# phy0.net
KiCad netlist of a schematic drawn in Altium Designer
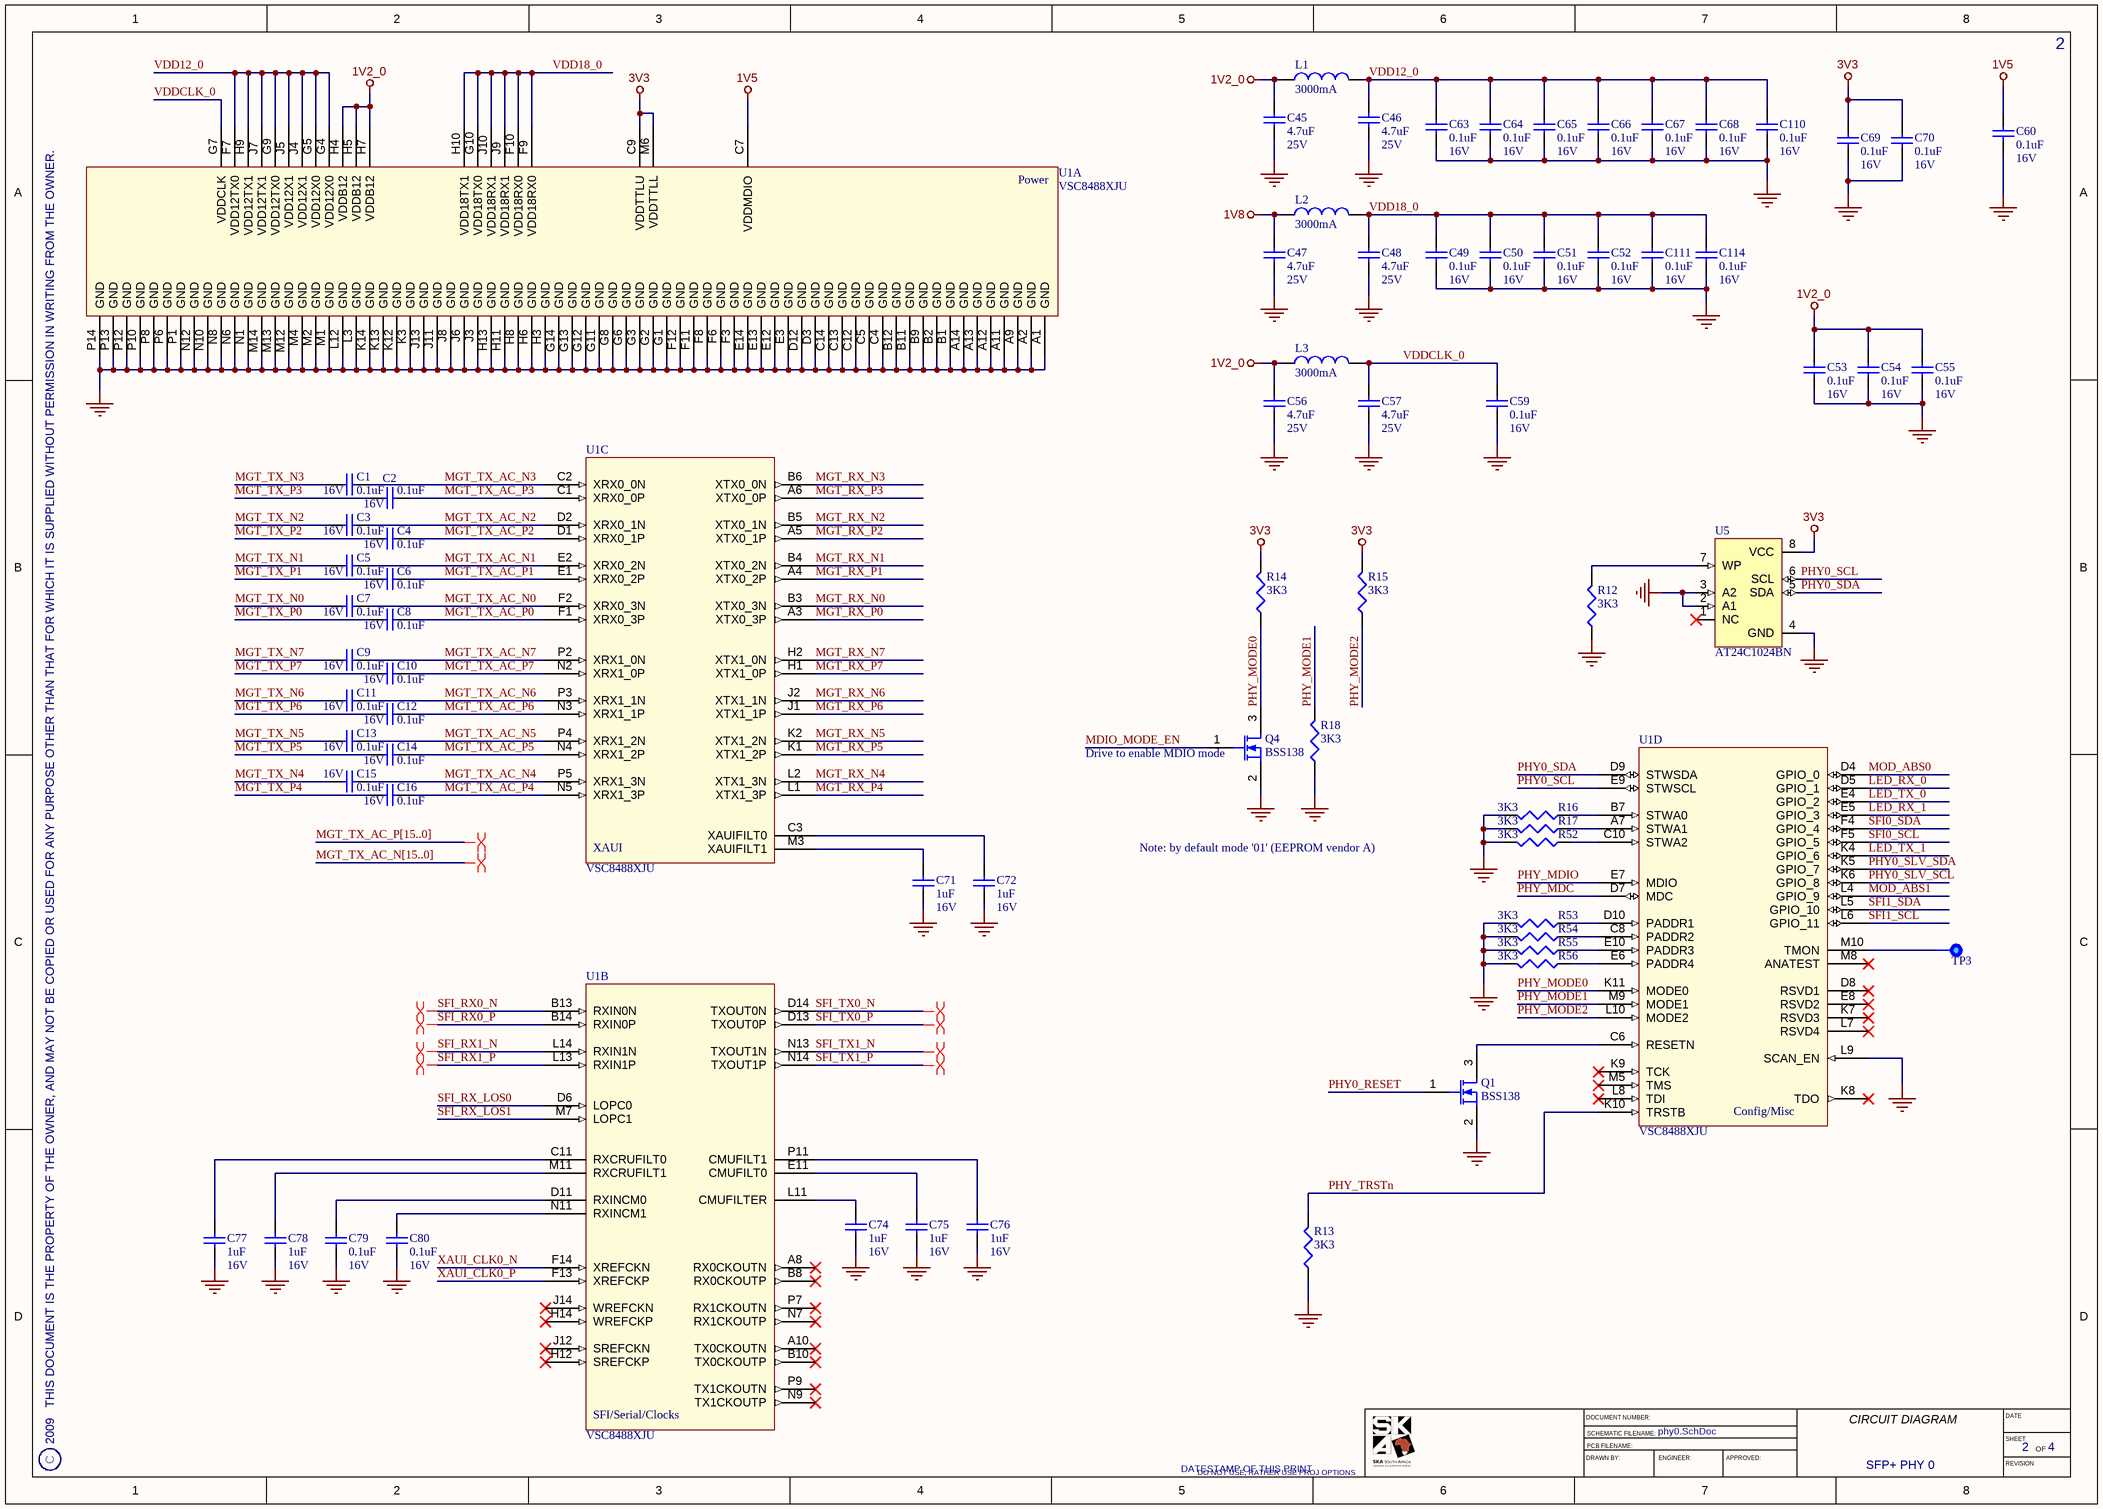
[diagram p0: phy0.SchDoc]

(export (version "E")
  (design (tool "Eeschema 10.0.6"))
  (components
    (comp (ref "C1")
      (value "0.1uF")
      (footprint "CAPC1005X60L")
      (description "0.1uF, Ceramic Capacitor")
      (fields
        (field (name "RATING") "16V")
        (field (name "MANUFACTURER") "VENKEL")
        (field (name "PARTNUM") "C0402X7R160-104KN")
      )
      (libsource (lib "altium_db") (part "CapStd"))
    )
    (comp (ref "C2")
      (value "0.1uF")
      (footprint "CAPC1005X60L")
      (description "0.1uF, Ceramic Capacitor")
      (fields
        (field (name "RATING") "16V")
        (field (name "MANUFACTURER") "VENKEL")
        (field (name "PARTNUM") "C0402X7R160-104KN")
      )
      (libsource (lib "altium_db") (part "CapStd"))
    )
    (comp (ref "C3")
      (value "0.1uF")
      (footprint "CAPC1005X60L")
      (description "0.1uF, Ceramic Capacitor")
      (fields
        (field (name "RATING") "16V")
        (field (name "MANUFACTURER") "VENKEL")
        (field (name "PARTNUM") "C0402X7R160-104KN")
      )
      (libsource (lib "altium_db") (part "CapStd"))
    )
    (comp (ref "C4")
      (value "0.1uF")
      (footprint "CAPC1005X60L")
      (description "0.1uF, Ceramic Capacitor")
      (fields
        (field (name "RATING") "16V")
        (field (name "MANUFACTURER") "VENKEL")
        (field (name "PARTNUM") "C0402X7R160-104KN")
      )
      (libsource (lib "altium_db") (part "CapStd"))
    )
    (comp (ref "C5")
      (value "0.1uF")
      (footprint "CAPC1005X60L")
      (description "0.1uF, Ceramic Capacitor")
      (fields
        (field (name "RATING") "16V")
        (field (name "MANUFACTURER") "VENKEL")
        (field (name "PARTNUM") "C0402X7R160-104KN")
      )
      (libsource (lib "altium_db") (part "CapStd"))
    )
    (comp (ref "C6")
      (value "0.1uF")
      (footprint "CAPC1005X60L")
      (description "0.1uF, Ceramic Capacitor")
      (fields
        (field (name "RATING") "16V")
        (field (name "MANUFACTURER") "VENKEL")
        (field (name "PARTNUM") "C0402X7R160-104KN")
      )
      (libsource (lib "altium_db") (part "CapStd"))
    )
    (comp (ref "C7")
      (value "0.1uF")
      (footprint "CAPC1005X60L")
      (description "0.1uF, Ceramic Capacitor")
      (fields
        (field (name "RATING") "16V")
        (field (name "MANUFACTURER") "VENKEL")
        (field (name "PARTNUM") "C0402X7R160-104KN")
      )
      (libsource (lib "altium_db") (part "CapStd"))
    )
    (comp (ref "C8")
      (value "0.1uF")
      (footprint "CAPC1005X60L")
      (description "0.1uF, Ceramic Capacitor")
      (fields
        (field (name "RATING") "16V")
        (field (name "MANUFACTURER") "VENKEL")
        (field (name "PARTNUM") "C0402X7R160-104KN")
      )
      (libsource (lib "altium_db") (part "CapStd"))
    )
    (comp (ref "C9")
      (value "0.1uF")
      (footprint "CAPC1005X60L")
      (description "0.1uF, Ceramic Capacitor")
      (fields
        (field (name "RATING") "16V")
        (field (name "MANUFACTURER") "VENKEL")
        (field (name "PARTNUM") "C0402X7R160-104KN")
      )
      (libsource (lib "altium_db") (part "CapStd"))
    )
    (comp (ref "C10")
      (value "0.1uF")
      (footprint "CAPC1005X60L")
      (description "0.1uF, Ceramic Capacitor")
      (fields
        (field (name "RATING") "16V")
        (field (name "MANUFACTURER") "VENKEL")
        (field (name "PARTNUM") "C0402X7R160-104KN")
      )
      (libsource (lib "altium_db") (part "CapStd"))
    )
    (comp (ref "C11")
      (value "0.1uF")
      (footprint "CAPC1005X60L")
      (description "0.1uF, Ceramic Capacitor")
      (fields
        (field (name "RATING") "16V")
        (field (name "MANUFACTURER") "VENKEL")
        (field (name "PARTNUM") "C0402X7R160-104KN")
      )
      (libsource (lib "altium_db") (part "CapStd"))
    )
    (comp (ref "C12")
      (value "0.1uF")
      (footprint "CAPC1005X60L")
      (description "0.1uF, Ceramic Capacitor")
      (fields
        (field (name "RATING") "16V")
        (field (name "MANUFACTURER") "VENKEL")
        (field (name "PARTNUM") "C0402X7R160-104KN")
      )
      (libsource (lib "altium_db") (part "CapStd"))
    )
    (comp (ref "C13")
      (value "0.1uF")
      (footprint "CAPC1005X60L")
      (description "0.1uF, Ceramic Capacitor")
      (fields
        (field (name "RATING") "16V")
        (field (name "MANUFACTURER") "VENKEL")
        (field (name "PARTNUM") "C0402X7R160-104KN")
      )
      (libsource (lib "altium_db") (part "CapStd"))
    )
    (comp (ref "C14")
      (value "0.1uF")
      (footprint "CAPC1005X60L")
      (description "0.1uF, Ceramic Capacitor")
      (fields
        (field (name "RATING") "16V")
        (field (name "MANUFACTURER") "VENKEL")
        (field (name "PARTNUM") "C0402X7R160-104KN")
      )
      (libsource (lib "altium_db") (part "CapStd"))
    )
    (comp (ref "C15")
      (value "0.1uF")
      (footprint "CAPC1005X60L")
      (description "0.1uF, Ceramic Capacitor")
      (fields
        (field (name "RATING") "16V")
        (field (name "MANUFACTURER") "VENKEL")
        (field (name "PARTNUM") "C0402X7R160-104KN")
      )
      (libsource (lib "altium_db") (part "CapStd"))
    )
    (comp (ref "C16")
      (value "0.1uF")
      (footprint "CAPC1005X60L")
      (description "0.1uF, Ceramic Capacitor")
      (fields
        (field (name "RATING") "16V")
        (field (name "MANUFACTURER") "VENKEL")
        (field (name "PARTNUM") "C0402X7R160-104KN")
      )
      (libsource (lib "altium_db") (part "CapStd"))
    )
    (comp (ref "C45")
      (value "4.7uF")
      (footprint "CAPC2012X127L")
      (description "4.7uF, Ceramic Capacitor")
      (fields
        (field (name "RATING") "25V")
        (field (name "MANUFACTURER") "MURATA")
        (field (name "PARTNUM") "GRM21BR61E475KA12K")
      )
      (libsource (lib "altium_db") (part "CapStd"))
    )
    (comp (ref "C46")
      (value "4.7uF")
      (footprint "CAPC2012X127L")
      (description "4.7uF, Ceramic Capacitor")
      (fields
        (field (name "RATING") "25V")
        (field (name "MANUFACTURER") "MURATA")
        (field (name "PARTNUM") "GRM21BR61E475KA12K")
      )
      (libsource (lib "altium_db") (part "CapStd"))
    )
    (comp (ref "C47")
      (value "4.7uF")
      (footprint "CAPC2012X127L")
      (description "4.7uF, Ceramic Capacitor")
      (fields
        (field (name "RATING") "25V")
        (field (name "MANUFACTURER") "MURATA")
        (field (name "PARTNUM") "GRM21BR61E475KA12K")
      )
      (libsource (lib "altium_db") (part "CapStd"))
    )
    (comp (ref "C48")
      (value "4.7uF")
      (footprint "CAPC2012X127L")
      (description "4.7uF, Ceramic Capacitor")
      (fields
        (field (name "RATING") "25V")
        (field (name "MANUFACTURER") "MURATA")
        (field (name "PARTNUM") "GRM21BR61E475KA12K")
      )
      (libsource (lib "altium_db") (part "CapStd"))
    )
    (comp (ref "C49")
      (value "0.1uF")
      (footprint "CAPC1005X60L")
      (description "0.1uF, Ceramic Capacitor")
      (fields
        (field (name "RATING") "16V")
        (field (name "MANUFACTURER") "VENKEL")
        (field (name "PARTNUM") "C0402X7R160-104KN")
      )
      (libsource (lib "altium_db") (part "CapStd"))
    )
    (comp (ref "C50")
      (value "0.1uF")
      (footprint "CAPC1005X60L")
      (description "0.1uF, Ceramic Capacitor")
      (fields
        (field (name "RATING") "16V")
        (field (name "MANUFACTURER") "VENKEL")
        (field (name "PARTNUM") "C0402X7R160-104KN")
      )
      (libsource (lib "altium_db") (part "CapStd"))
    )
    (comp (ref "C51")
      (value "0.1uF")
      (footprint "CAPC1005X60L")
      (description "0.1uF, Ceramic Capacitor")
      (fields
        (field (name "RATING") "16V")
        (field (name "MANUFACTURER") "VENKEL")
        (field (name "PARTNUM") "C0402X7R160-104KN")
      )
      (libsource (lib "altium_db") (part "CapStd"))
    )
    (comp (ref "C52")
      (value "0.1uF")
      (footprint "CAPC1005X60L")
      (description "0.1uF, Ceramic Capacitor")
      (fields
        (field (name "RATING") "16V")
        (field (name "MANUFACTURER") "VENKEL")
        (field (name "PARTNUM") "C0402X7R160-104KN")
      )
      (libsource (lib "altium_db") (part "CapStd"))
    )
    (comp (ref "C53")
      (value "0.1uF")
      (footprint "CAPC1005X60L")
      (description "0.1uF, Ceramic Capacitor")
      (fields
        (field (name "RATING") "16V")
        (field (name "MANUFACTURER") "VENKEL")
        (field (name "PARTNUM") "C0402X7R160-104KN")
      )
      (libsource (lib "altium_db") (part "CapStd"))
    )
    (comp (ref "C54")
      (value "0.1uF")
      (footprint "CAPC1005X60L")
      (description "0.1uF, Ceramic Capacitor")
      (fields
        (field (name "RATING") "16V")
        (field (name "MANUFACTURER") "VENKEL")
        (field (name "PARTNUM") "C0402X7R160-104KN")
      )
      (libsource (lib "altium_db") (part "CapStd"))
    )
    (comp (ref "C55")
      (value "0.1uF")
      (footprint "CAPC1005X60L")
      (description "0.1uF, Ceramic Capacitor")
      (fields
        (field (name "RATING") "16V")
        (field (name "MANUFACTURER") "VENKEL")
        (field (name "PARTNUM") "C0402X7R160-104KN")
      )
      (libsource (lib "altium_db") (part "CapStd"))
    )
    (comp (ref "C56")
      (value "4.7uF")
      (footprint "CAPC2012X127L")
      (description "4.7uF, Ceramic Capacitor")
      (fields
        (field (name "RATING") "25V")
        (field (name "MANUFACTURER") "MURATA")
        (field (name "PARTNUM") "GRM21BR61E475KA12K")
      )
      (libsource (lib "altium_db") (part "CapStd"))
    )
    (comp (ref "C57")
      (value "4.7uF")
      (footprint "CAPC2012X127L")
      (description "4.7uF, Ceramic Capacitor")
      (fields
        (field (name "RATING") "25V")
        (field (name "MANUFACTURER") "MURATA")
        (field (name "PARTNUM") "GRM21BR61E475KA12K")
      )
      (libsource (lib "altium_db") (part "CapStd"))
    )
    (comp (ref "C59")
      (value "0.1uF")
      (footprint "CAPC1005X60L")
      (description "0.1uF, Ceramic Capacitor")
      (fields
        (field (name "RATING") "16V")
        (field (name "MANUFACTURER") "VENKEL")
        (field (name "PARTNUM") "C0402X7R160-104KN")
      )
      (libsource (lib "altium_db") (part "CapStd"))
    )
    (comp (ref "C60")
      (value "0.1uF")
      (footprint "CAPC1005X60L")
      (description "0.1uF, Ceramic Capacitor")
      (fields
        (field (name "RATING") "16V")
        (field (name "MANUFACTURER") "VENKEL")
        (field (name "PARTNUM") "C0402X7R160-104KN")
      )
      (libsource (lib "altium_db") (part "CapStd"))
    )
    (comp (ref "C63")
      (value "0.1uF")
      (footprint "CAPC1005X60L")
      (description "0.1uF, Ceramic Capacitor")
      (fields
        (field (name "RATING") "16V")
        (field (name "MANUFACTURER") "VENKEL")
        (field (name "PARTNUM") "C0402X7R160-104KN")
      )
      (libsource (lib "altium_db") (part "CapStd"))
    )
    (comp (ref "C64")
      (value "0.1uF")
      (footprint "CAPC1005X60L")
      (description "0.1uF, Ceramic Capacitor")
      (fields
        (field (name "RATING") "16V")
        (field (name "MANUFACTURER") "VENKEL")
        (field (name "PARTNUM") "C0402X7R160-104KN")
      )
      (libsource (lib "altium_db") (part "CapStd"))
    )
    (comp (ref "C65")
      (value "0.1uF")
      (footprint "CAPC1005X60L")
      (description "0.1uF, Ceramic Capacitor")
      (fields
        (field (name "RATING") "16V")
        (field (name "MANUFACTURER") "VENKEL")
        (field (name "PARTNUM") "C0402X7R160-104KN")
      )
      (libsource (lib "altium_db") (part "CapStd"))
    )
    (comp (ref "C66")
      (value "0.1uF")
      (footprint "CAPC1005X60L")
      (description "0.1uF, Ceramic Capacitor")
      (fields
        (field (name "RATING") "16V")
        (field (name "MANUFACTURER") "VENKEL")
        (field (name "PARTNUM") "C0402X7R160-104KN")
      )
      (libsource (lib "altium_db") (part "CapStd"))
    )
    (comp (ref "C67")
      (value "0.1uF")
      (footprint "CAPC1005X60L")
      (description "0.1uF, Ceramic Capacitor")
      (fields
        (field (name "RATING") "16V")
        (field (name "MANUFACTURER") "VENKEL")
        (field (name "PARTNUM") "C0402X7R160-104KN")
      )
      (libsource (lib "altium_db") (part "CapStd"))
    )
    (comp (ref "C68")
      (value "0.1uF")
      (footprint "CAPC1005X60L")
      (description "0.1uF, Ceramic Capacitor")
      (fields
        (field (name "RATING") "16V")
        (field (name "MANUFACTURER") "VENKEL")
        (field (name "PARTNUM") "C0402X7R160-104KN")
      )
      (libsource (lib "altium_db") (part "CapStd"))
    )
    (comp (ref "C69")
      (value "0.1uF")
      (footprint "CAPC1005X60L")
      (description "0.1uF, Ceramic Capacitor")
      (fields
        (field (name "RATING") "16V")
        (field (name "MANUFACTURER") "VENKEL")
        (field (name "PARTNUM") "C0402X7R160-104KN")
      )
      (libsource (lib "altium_db") (part "CapStd"))
    )
    (comp (ref "C70")
      (value "0.1uF")
      (footprint "CAPC1005X60L")
      (description "0.1uF, Ceramic Capacitor")
      (fields
        (field (name "RATING") "16V")
        (field (name "MANUFACTURER") "VENKEL")
        (field (name "PARTNUM") "C0402X7R160-104KN")
      )
      (libsource (lib "altium_db") (part "CapStd"))
    )
    (comp (ref "C71")
      (value "1uF")
      (footprint "CAPC2012X127L")
      (description "1uF, Ceramic Capacitor")
      (fields
        (field (name "RATING") "16V")
        (field (name "MANUFACTURER") "MURATA")
        (field (name "PARTNUM") "GRM21BR61C105KA01L")
      )
      (libsource (lib "altium_db") (part "CapStd"))
    )
    (comp (ref "C72")
      (value "1uF")
      (footprint "CAPC2012X127L")
      (description "1uF, Ceramic Capacitor")
      (fields
        (field (name "RATING") "16V")
        (field (name "MANUFACTURER") "MURATA")
        (field (name "PARTNUM") "GRM21BR61C105KA01L")
      )
      (libsource (lib "altium_db") (part "CapStd"))
    )
    (comp (ref "C74")
      (value "1uF")
      (footprint "CAPC2012X127L")
      (description "1uF, Ceramic Capacitor")
      (fields
        (field (name "RATING") "16V")
        (field (name "MANUFACTURER") "MURATA")
        (field (name "PARTNUM") "GRM21BR61C105KA01L")
      )
      (libsource (lib "altium_db") (part "CapStd"))
    )
    (comp (ref "C75")
      (value "1uF")
      (footprint "CAPC2012X127L")
      (description "1uF, Ceramic Capacitor")
      (fields
        (field (name "RATING") "16V")
        (field (name "MANUFACTURER") "MURATA")
        (field (name "PARTNUM") "GRM21BR61C105KA01L")
      )
      (libsource (lib "altium_db") (part "CapStd"))
    )
    (comp (ref "C76")
      (value "1uF")
      (footprint "CAPC2012X127L")
      (description "1uF, Ceramic Capacitor")
      (fields
        (field (name "RATING") "16V")
        (field (name "MANUFACTURER") "MURATA")
        (field (name "PARTNUM") "GRM21BR61C105KA01L")
      )
      (libsource (lib "altium_db") (part "CapStd"))
    )
    (comp (ref "C77")
      (value "1uF")
      (footprint "CAPC2012X127L")
      (description "1uF, Ceramic Capacitor")
      (fields
        (field (name "RATING") "16V")
        (field (name "MANUFACTURER") "MURATA")
        (field (name "PARTNUM") "GRM21BR61C105KA01L")
      )
      (libsource (lib "altium_db") (part "CapStd"))
    )
    (comp (ref "C78")
      (value "1uF")
      (footprint "CAPC2012X127L")
      (description "1uF, Ceramic Capacitor")
      (fields
        (field (name "RATING") "16V")
        (field (name "MANUFACTURER") "MURATA")
        (field (name "PARTNUM") "GRM21BR61C105KA01L")
      )
      (libsource (lib "altium_db") (part "CapStd"))
    )
    (comp (ref "C79")
      (value "0.1uF")
      (footprint "CAPC1005X60L")
      (description "0.1uF, Ceramic Capacitor")
      (fields
        (field (name "RATING") "16V")
        (field (name "MANUFACTURER") "VENKEL")
        (field (name "PARTNUM") "C0402X7R160-104KN")
      )
      (libsource (lib "altium_db") (part "CapStd"))
    )
    (comp (ref "C80")
      (value "0.1uF")
      (footprint "CAPC1005X60L")
      (description "0.1uF, Ceramic Capacitor")
      (fields
        (field (name "RATING") "16V")
        (field (name "MANUFACTURER") "VENKEL")
        (field (name "PARTNUM") "C0402X7R160-104KN")
      )
      (libsource (lib "altium_db") (part "CapStd"))
    )
    (comp (ref "C110")
      (value "0.1uF")
      (footprint "CAPC1005X60L")
      (description "0.1uF, Ceramic Capacitor")
      (fields
        (field (name "RATING") "16V")
        (field (name "MANUFACTURER") "VENKEL")
        (field (name "PARTNUM") "C0402X7R160-104KN")
      )
      (libsource (lib "altium_db") (part "CapStd"))
    )
    (comp (ref "C111")
      (value "0.1uF")
      (footprint "CAPC1005X60L")
      (description "0.1uF, Ceramic Capacitor")
      (fields
        (field (name "RATING") "16V")
        (field (name "MANUFACTURER") "VENKEL")
        (field (name "PARTNUM") "C0402X7R160-104KN")
      )
      (libsource (lib "altium_db") (part "CapStd"))
    )
    (comp (ref "C114")
      (value "0.1uF")
      (footprint "CAPC1005X60L")
      (description "0.1uF, Ceramic Capacitor")
      (fields
        (field (name "RATING") "16V")
        (field (name "MANUFACTURER") "VENKEL")
        (field (name "PARTNUM") "C0402X7R160-104KN")
      )
      (libsource (lib "altium_db") (part "CapStd"))
    )
    (comp (ref "L1")
      (value "120R")
      (footprint "INDC3216X130L")
      (description "120 Ohm, Chip Ferrite Brad")
      (fields
        (field (name "RATING") "3000mA")
        (field (name "MANUFACTURER") "Murata")
        (field (name "PARTNUM") "BLM31PG121SN1")
      )
      (libsource (lib "altium_db") (part "IndStd"))
    )
    (comp (ref "L2")
      (value "120R")
      (footprint "INDC3216X130L")
      (description "120 Ohm, Chip Ferrite Brad")
      (fields
        (field (name "RATING") "3000mA")
        (field (name "MANUFACTURER") "Murata")
        (field (name "PARTNUM") "BLM31PG121SN1")
      )
      (libsource (lib "altium_db") (part "IndStd"))
    )
    (comp (ref "L3")
      (value "120R")
      (footprint "INDC3216X130L")
      (description "120 Ohm, Chip Ferrite Brad")
      (fields
        (field (name "RATING") "3000mA")
        (field (name "MANUFACTURER") "Murata")
        (field (name "PARTNUM") "BLM31PG121SN1")
      )
      (libsource (lib "altium_db") (part "IndStd"))
    )
    (comp (ref "Q1")
      (value "BSS138")
      (footprint "SOT95P245X110-3N")
      (description "N-Channel Logic Level Enhancement Mode Field Effect Transistor")
      (fields (field (name "MANUFACTURER") "Fairchild Semiconductor"))
      (libsource (lib "altium_db") (part "BSS138"))
    )
    (comp (ref "Q4")
      (value "BSS138")
      (footprint "SOT95P245X110-3N")
      (description "N-Channel Logic Level Enhancement Mode Field Effect Transistor")
      (fields (field (name "MANUFACTURER") "Fairchild Semiconductor"))
      (libsource (lib "altium_db") (part "BSS138"))
    )
    (comp (ref "R12")
      (value "3K3")
      (footprint "RESC1005X40L")
      (description "3K3, 1.1mm x 0.5mm, Thick Film Resistor")
      (fields (field (name "MANUFACTURER") "ROYALOHM") (field (name "PARTNUM") "0402WGJ0332T1E"))
      (libsource (lib "altium_db") (part "ResStd"))
    )
    (comp (ref "R13")
      (value "3K3")
      (footprint "RESC1005X40L")
      (description "3K3, 1.1mm x 0.5mm, Thick Film Resistor")
      (fields (field (name "MANUFACTURER") "ROYALOHM") (field (name "PARTNUM") "0402WGJ0332T1E"))
      (libsource (lib "altium_db") (part "ResStd"))
    )
    (comp (ref "R14")
      (value "3K3")
      (footprint "RESC1005X40L")
      (description "3K3, 1.1mm x 0.5mm, Thick Film Resistor")
      (fields (field (name "MANUFACTURER") "ROYALOHM") (field (name "PARTNUM") "0402WGJ0332T1E"))
      (libsource (lib "altium_db") (part "ResStd"))
    )
    (comp (ref "R15")
      (value "3K3")
      (footprint "RESC1005X40L")
      (description "3K3, 1.1mm x 0.5mm, Thick Film Resistor")
      (fields (field (name "MANUFACTURER") "ROYALOHM") (field (name "PARTNUM") "0402WGJ0332T1E"))
      (libsource (lib "altium_db") (part "ResStd"))
    )
    (comp (ref "R16")
      (value "3K3")
      (footprint "RESC1005X40L")
      (description "3K3, 1.1mm x 0.5mm, Thick Film Resistor")
      (fields (field (name "MANUFACTURER") "ROYALOHM") (field (name "PARTNUM") "0402WGJ0332T1E"))
      (libsource (lib "altium_db") (part "ResStd"))
    )
    (comp (ref "R17")
      (value "3K3")
      (footprint "RESC1005X40L")
      (description "3K3, 1.1mm x 0.5mm, Thick Film Resistor")
      (fields (field (name "MANUFACTURER") "ROYALOHM") (field (name "PARTNUM") "0402WGJ0332T1E"))
      (libsource (lib "altium_db") (part "ResStd"))
    )
    (comp (ref "R18")
      (value "3K3")
      (footprint "RESC1005X40L")
      (description "3K3, 1.1mm x 0.5mm, Thick Film Resistor")
      (fields (field (name "MANUFACTURER") "ROYALOHM") (field (name "PARTNUM") "0402WGJ0332T1E"))
      (libsource (lib "altium_db") (part "ResStd"))
    )
    (comp (ref "R52")
      (value "3K3")
      (footprint "RESC1005X40L")
      (description "3K3, 1.1mm x 0.5mm, Thick Film Resistor")
      (fields (field (name "MANUFACTURER") "ROYALOHM") (field (name "PARTNUM") "0402WGJ0332T1E"))
      (libsource (lib "altium_db") (part "ResStd"))
    )
    (comp (ref "R53")
      (value "3K3")
      (footprint "RESC1005X40L")
      (description "3K3, 1.1mm x 0.5mm, Thick Film Resistor")
      (fields (field (name "MANUFACTURER") "ROYALOHM") (field (name "PARTNUM") "0402WGJ0332T1E"))
      (libsource (lib "altium_db") (part "ResStd"))
    )
    (comp (ref "R54")
      (value "3K3")
      (footprint "RESC1005X40L")
      (description "3K3, 1.1mm x 0.5mm, Thick Film Resistor")
      (fields (field (name "MANUFACTURER") "ROYALOHM") (field (name "PARTNUM") "0402WGJ0332T1E"))
      (libsource (lib "altium_db") (part "ResStd"))
    )
    (comp (ref "R55")
      (value "3K3")
      (footprint "RESC1005X40L")
      (description "3K3, 1.1mm x 0.5mm, Thick Film Resistor")
      (fields (field (name "MANUFACTURER") "ROYALOHM") (field (name "PARTNUM") "0402WGJ0332T1E"))
      (libsource (lib "altium_db") (part "ResStd"))
    )
    (comp (ref "R56")
      (value "3K3")
      (footprint "RESC1005X40L")
      (description "3K3, 1.1mm x 0.5mm, Thick Film Resistor")
      (fields (field (name "MANUFACTURER") "ROYALOHM") (field (name "PARTNUM") "0402WGJ0332T1E"))
      (libsource (lib "altium_db") (part "ResStd"))
    )
    (comp (ref "TP3")
      (value "Testpoint")
      (footprint "TP100")
      (description "1mm Diameter, through-hole, Circular Test-point")
      (libsource (lib "altium_db") (part "Testpoint"))
    )
    (comp (ref "U1")
      (value "VSC8488XJU")
      (footprint "BGA196C100P14X14_1500x1500x140")
      (description "DualChannel WAN/LAN/Backplane XAUI to SFP+/KR Transceiver")
      (fields (field (name "MANUFACTURER") "Vitesse"))
      (libsource (lib "altium_db") (part "VSC8488XJU"))
    )
    (comp (ref "U5")
      (value "AT24C1024BN")
      (footprint "SOIC150-8_N")
      (description "1M, SOIC-8, Serial EEPROM")
      (fields (field (name "MANUFACTURER") "Atmel") (field (name "PARTNUM") "AT24C1024BN-SH-B"))
      (libsource (lib "altium_db") (part "AT24C1024BN-SH"))
    )
  )
  (nets
    (net (code "17") (name "/LED_RX_0") (class "Default")
      (node (ref "U1") (pin "D5") (pinfunction "GPIO_1_D5") (pintype "bidirectional"))
    )
    (net (code "18") (name "/LED_RX_1") (class "Default")
      (node (ref "U1") (pin "E5") (pinfunction "GPIO_3_E5") (pintype "bidirectional"))
    )
    (net (code "19") (name "/LED_TX_0") (class "Default")
      (node (ref "U1") (pin "E4") (pinfunction "GPIO_2_E4") (pintype "bidirectional"))
    )
    (net (code "20") (name "/LED_TX_1") (class "Default")
      (node (ref "U1") (pin "K4") (pinfunction "GPIO_6_K4") (pintype "bidirectional"))
    )
    (net (code "21") (name "/MDIO_MODE_EN") (class "Default")
      (node (ref "Q4") (pin "1") (pinfunction "G_1") (pintype "passive"))
    )
    (net (code "22") (name "/MGT_RX_N0") (class "Default")
      (node (ref "U1") (pin "B3") (pinfunction "XTX0_3N_B3") (pintype "output"))
    )
    (net (code "23") (name "/MGT_RX_N1") (class "Default")
      (node (ref "U1") (pin "B4") (pinfunction "XTX0_2N_B4") (pintype "output"))
    )
    (net (code "24") (name "/MGT_RX_N2") (class "Default")
      (node (ref "U1") (pin "B5") (pinfunction "XTX0_1N_B5") (pintype "output"))
    )
    (net (code "25") (name "/MGT_RX_N3") (class "Default")
      (node (ref "U1") (pin "B6") (pinfunction "XTX0_0N_B6") (pintype "output"))
    )
    (net (code "26") (name "/MGT_RX_N4") (class "Default")
      (node (ref "U1") (pin "L2") (pinfunction "XTX1_3N_L2") (pintype "output"))
    )
    (net (code "27") (name "/MGT_RX_N5") (class "Default")
      (node (ref "U1") (pin "K2") (pinfunction "XTX1_2N_K2") (pintype "output"))
    )
    (net (code "28") (name "/MGT_RX_N6") (class "Default")
      (node (ref "U1") (pin "J2") (pinfunction "XTX1_1N_J2") (pintype "output"))
    )
    (net (code "29") (name "/MGT_RX_N7") (class "Default")
      (node (ref "U1") (pin "H2") (pinfunction "XTX1_0N_H2") (pintype "output"))
    )
    (net (code "30") (name "/MGT_RX_P0") (class "Default")
      (node (ref "U1") (pin "A3") (pinfunction "XTX0_3P_A3") (pintype "output"))
    )
    (net (code "31") (name "/MGT_RX_P1") (class "Default")
      (node (ref "U1") (pin "A4") (pinfunction "XTX0_2P_A4") (pintype "output"))
    )
    (net (code "32") (name "/MGT_RX_P2") (class "Default")
      (node (ref "U1") (pin "A5") (pinfunction "XTX0_1P_A5") (pintype "output"))
    )
    (net (code "33") (name "/MGT_RX_P3") (class "Default")
      (node (ref "U1") (pin "A6") (pinfunction "XTX0_0P_A6") (pintype "output"))
    )
    (net (code "34") (name "/MGT_RX_P4") (class "Default")
      (node (ref "U1") (pin "L1") (pinfunction "XTX1_3P_L1") (pintype "output"))
    )
    (net (code "35") (name "/MGT_RX_P5") (class "Default")
      (node (ref "U1") (pin "K1") (pinfunction "XTX1_2P_K1") (pintype "output"))
    )
    (net (code "36") (name "/MGT_RX_P6") (class "Default")
      (node (ref "U1") (pin "J1") (pinfunction "XTX1_1P_J1") (pintype "output"))
    )
    (net (code "37") (name "/MGT_RX_P7") (class "Default")
      (node (ref "U1") (pin "H1") (pinfunction "XTX1_0P_H1") (pintype "output"))
    )
    (net (code "38") (name "/MGT_TX_AC_N0") (class "Default")
      (node (ref "C7") (pin "1") (pinfunction "1_1") (pintype "passive"))
      (node (ref "U1") (pin "F2") (pinfunction "XRX0_3N_F2") (pintype "input"))
    )
    (net (code "39") (name "/MGT_TX_AC_N1") (class "Default")
      (node (ref "C5") (pin "1") (pinfunction "1_1") (pintype "passive"))
      (node (ref "U1") (pin "E2") (pinfunction "XRX0_2N_E2") (pintype "input"))
    )
    (net (code "40") (name "/MGT_TX_AC_N2") (class "Default")
      (node (ref "C3") (pin "1") (pinfunction "1_1") (pintype "passive"))
      (node (ref "U1") (pin "D2") (pinfunction "XRX0_1N_D2") (pintype "input"))
    )
    (net (code "41") (name "/MGT_TX_AC_N3") (class "Default")
      (node (ref "C1") (pin "1") (pinfunction "1_1") (pintype "passive"))
      (node (ref "U1") (pin "C2") (pinfunction "XRX0_0N_C2") (pintype "input"))
    )
    (net (code "42") (name "/MGT_TX_AC_N4") (class "Default")
      (node (ref "C15") (pin "1") (pinfunction "1_1") (pintype "passive"))
      (node (ref "U1") (pin "P5") (pinfunction "XRX1_3N_P5") (pintype "input"))
    )
    (net (code "43") (name "/MGT_TX_AC_N5") (class "Default")
      (node (ref "C13") (pin "1") (pinfunction "1_1") (pintype "passive"))
      (node (ref "U1") (pin "P4") (pinfunction "XRX1_2N_P4") (pintype "input"))
    )
    (net (code "44") (name "/MGT_TX_AC_N6") (class "Default")
      (node (ref "C11") (pin "1") (pinfunction "1_1") (pintype "passive"))
      (node (ref "U1") (pin "P3") (pinfunction "XRX1_1N_P3") (pintype "input"))
    )
    (net (code "45") (name "/MGT_TX_AC_N7") (class "Default")
      (node (ref "C9") (pin "1") (pinfunction "1_1") (pintype "passive"))
      (node (ref "U1") (pin "P2") (pinfunction "XRX1_0N_P2") (pintype "input"))
    )
    (net (code "47") (name "/MGT_TX_AC_P0") (class "Default")
      (node (ref "C8") (pin "1") (pinfunction "1_1") (pintype "passive"))
      (node (ref "U1") (pin "F1") (pinfunction "XRX0_3P_F1") (pintype "input"))
    )
    (net (code "48") (name "/MGT_TX_AC_P1") (class "Default")
      (node (ref "C6") (pin "1") (pinfunction "1_1") (pintype "passive"))
      (node (ref "U1") (pin "E1") (pinfunction "XRX0_2P_E1") (pintype "input"))
    )
    (net (code "49") (name "/MGT_TX_AC_P2") (class "Default")
      (node (ref "C4") (pin "1") (pinfunction "1_1") (pintype "passive"))
      (node (ref "U1") (pin "D1") (pinfunction "XRX0_1P_D1") (pintype "input"))
    )
    (net (code "50") (name "/MGT_TX_AC_P3") (class "Default")
      (node (ref "C2") (pin "1") (pinfunction "1_1") (pintype "passive"))
      (node (ref "U1") (pin "C1") (pinfunction "XRX0_0P_C1") (pintype "input"))
    )
    (net (code "51") (name "/MGT_TX_AC_P4") (class "Default")
      (node (ref "C16") (pin "1") (pinfunction "1_1") (pintype "passive"))
      (node (ref "U1") (pin "N5") (pinfunction "XRX1_3P_N5") (pintype "input"))
    )
    (net (code "52") (name "/MGT_TX_AC_P5") (class "Default")
      (node (ref "C14") (pin "1") (pinfunction "1_1") (pintype "passive"))
      (node (ref "U1") (pin "N4") (pinfunction "XRX1_2P_N4") (pintype "input"))
    )
    (net (code "53") (name "/MGT_TX_AC_P6") (class "Default")
      (node (ref "C12") (pin "1") (pinfunction "1_1") (pintype "passive"))
      (node (ref "U1") (pin "N3") (pinfunction "XRX1_1P_N3") (pintype "input"))
    )
    (net (code "54") (name "/MGT_TX_AC_P7") (class "Default")
      (node (ref "C10") (pin "1") (pinfunction "1_1") (pintype "passive"))
      (node (ref "U1") (pin "N2") (pinfunction "XRX1_0P_N2") (pintype "input"))
    )
    (net (code "56") (name "/MGT_TX_N0") (class "Default")
      (node (ref "C7") (pin "2") (pinfunction "2_2") (pintype "passive"))
    )
    (net (code "57") (name "/MGT_TX_N1") (class "Default")
      (node (ref "C5") (pin "2") (pinfunction "2_2") (pintype "passive"))
    )
    (net (code "58") (name "/MGT_TX_N2") (class "Default")
      (node (ref "C3") (pin "2") (pinfunction "2_2") (pintype "passive"))
    )
    (net (code "59") (name "/MGT_TX_N3") (class "Default")
      (node (ref "C1") (pin "2") (pinfunction "2_2") (pintype "passive"))
    )
    (net (code "60") (name "/MGT_TX_N4") (class "Default")
      (node (ref "C15") (pin "2") (pinfunction "2_2") (pintype "passive"))
    )
    (net (code "61") (name "/MGT_TX_N5") (class "Default")
      (node (ref "C13") (pin "2") (pinfunction "2_2") (pintype "passive"))
    )
    (net (code "62") (name "/MGT_TX_N6") (class "Default")
      (node (ref "C11") (pin "2") (pinfunction "2_2") (pintype "passive"))
    )
    (net (code "63") (name "/MGT_TX_N7") (class "Default")
      (node (ref "C9") (pin "2") (pinfunction "2_2") (pintype "passive"))
    )
    (net (code "64") (name "/MGT_TX_P0") (class "Default")
      (node (ref "C8") (pin "2") (pinfunction "2_2") (pintype "passive"))
    )
    (net (code "65") (name "/MGT_TX_P1") (class "Default")
      (node (ref "C6") (pin "2") (pinfunction "2_2") (pintype "passive"))
    )
    (net (code "66") (name "/MGT_TX_P2") (class "Default")
      (node (ref "C4") (pin "2") (pinfunction "2_2") (pintype "passive"))
    )
    (net (code "67") (name "/MGT_TX_P3") (class "Default")
      (node (ref "C2") (pin "2") (pinfunction "2_2") (pintype "passive"))
    )
    (net (code "68") (name "/MGT_TX_P4") (class "Default")
      (node (ref "C16") (pin "2") (pinfunction "2_2") (pintype "passive"))
    )
    (net (code "69") (name "/MGT_TX_P5") (class "Default")
      (node (ref "C14") (pin "2") (pinfunction "2_2") (pintype "passive"))
    )
    (net (code "70") (name "/MGT_TX_P6") (class "Default")
      (node (ref "C12") (pin "2") (pinfunction "2_2") (pintype "passive"))
    )
    (net (code "71") (name "/MGT_TX_P7") (class "Default")
      (node (ref "C10") (pin "2") (pinfunction "2_2") (pintype "passive"))
    )
    (net (code "72") (name "/MOD_ABS0") (class "Default")
      (node (ref "U1") (pin "D4") (pinfunction "GPIO_0_D4") (pintype "bidirectional"))
    )
    (net (code "73") (name "/MOD_ABS1") (class "Default")
      (node (ref "U1") (pin "L4") (pinfunction "GPIO_9_L4") (pintype "bidirectional"))
    )
    (net (code "74") (name "/PHY0_RESET") (class "Default")
      (node (ref "Q1") (pin "1") (pinfunction "G_1") (pintype "passive"))
    )
    (net (code "75") (name "/PHY0_SCL") (class "Default")
      (node (ref "U1") (pin "E9") (pinfunction "STWSCL_E9") (pintype "bidirectional"))
      (node (ref "U5") (pin "6") (pinfunction "SCL_6") (pintype "bidirectional"))
    )
    (net (code "76") (name "/PHY0_SDA") (class "Default")
      (node (ref "U1") (pin "D9") (pinfunction "STWSDA_D9") (pintype "bidirectional"))
      (node (ref "U5") (pin "5") (pinfunction "SDA_5") (pintype "bidirectional"))
    )
    (net (code "77") (name "/PHY0_SLV_SCL") (class "Default")
      (node (ref "U1") (pin "K6") (pinfunction "GPIO_8_K6") (pintype "bidirectional"))
    )
    (net (code "78") (name "/PHY0_SLV_SDA") (class "Default")
      (node (ref "U1") (pin "K5") (pinfunction "GPIO_7_K5") (pintype "bidirectional"))
    )
    (net (code "79") (name "/PHY_MDC") (class "Default")
      (node (ref "U1") (pin "D7") (pinfunction "MDC_D7") (pintype "bidirectional"))
    )
    (net (code "80") (name "/PHY_MDIO") (class "Default")
      (node (ref "U1") (pin "E7") (pinfunction "MDIO_E7") (pintype "input"))
    )
    (net (code "81") (name "/PHY_MODE0") (class "Default")
      (node (ref "Q4") (pin "3") (pinfunction "D_3") (pintype "passive"))
      (node (ref "R14") (pin "1") (pinfunction "1_1") (pintype "passive"))
      (node (ref "U1") (pin "K11") (pinfunction "MODE0_K11") (pintype "input"))
    )
    (net (code "82") (name "/PHY_MODE1") (class "Default")
      (node (ref "R18") (pin "2") (pinfunction "2_2") (pintype "passive"))
      (node (ref "U1") (pin "M9") (pinfunction "MODE1_M9") (pintype "input"))
    )
    (net (code "83") (name "/PHY_MODE2") (class "Default")
      (node (ref "R15") (pin "1") (pinfunction "1_1") (pintype "passive"))
      (node (ref "U1") (pin "L10") (pinfunction "MODE2_L10") (pintype "input"))
    )
    (net (code "84") (name "/PHY_TRSTn") (class "Default")
      (node (ref "R13") (pin "2") (pinfunction "2_2") (pintype "passive"))
      (node (ref "U1") (pin "K10") (pinfunction "TRSTB_K10") (pintype "input"))
    )
    (net (code "85") (name "/SFI0_SCL") (class "Default")
      (node (ref "U1") (pin "F5") (pinfunction "GPIO_5_F5") (pintype "bidirectional"))
    )
    (net (code "86") (name "/SFI0_SDA") (class "Default")
      (node (ref "U1") (pin "F4") (pinfunction "GPIO_4_F4") (pintype "bidirectional"))
    )
    (net (code "87") (name "/SFI1_SCL") (class "Default")
      (node (ref "U1") (pin "L6") (pinfunction "GPIO_11_L6") (pintype "bidirectional"))
    )
    (net (code "88") (name "/SFI1_SDA") (class "Default")
      (node (ref "U1") (pin "L5") (pinfunction "GPIO_10_L5") (pintype "bidirectional"))
    )
    (net (code "89") (name "/SFI_RX0_N") (class "Default")
      (node (ref "U1") (pin "B13") (pinfunction "RXIN0N_B13") (pintype "input"))
    )
    (net (code "90") (name "/SFI_RX0_P") (class "Default")
      (node (ref "U1") (pin "B14") (pinfunction "RXIN0P_B14") (pintype "input"))
    )
    (net (code "91") (name "/SFI_RX1_N") (class "Default")
      (node (ref "U1") (pin "L14") (pinfunction "RXIN1N_L14") (pintype "input"))
    )
    (net (code "92") (name "/SFI_RX1_P") (class "Default")
      (node (ref "U1") (pin "L13") (pinfunction "RXIN1P_L13") (pintype "input"))
    )
    (net (code "93") (name "/SFI_RX_LOS0") (class "Default")
      (node (ref "U1") (pin "D6") (pinfunction "LOPC0_D6") (pintype "input"))
    )
    (net (code "94") (name "/SFI_RX_LOS1") (class "Default")
      (node (ref "U1") (pin "M7") (pinfunction "LOPC1_M7") (pintype "input"))
    )
    (net (code "95") (name "/SFI_TX0_N") (class "Default")
      (node (ref "U1") (pin "D14") (pinfunction "TXOUT0N_D14") (pintype "output"))
    )
    (net (code "96") (name "/SFI_TX0_P") (class "Default")
      (node (ref "U1") (pin "D13") (pinfunction "TXOUT0P_D13") (pintype "output"))
    )
    (net (code "97") (name "/SFI_TX1_N") (class "Default")
      (node (ref "U1") (pin "N13") (pinfunction "TXOUT1N_N13") (pintype "output"))
    )
    (net (code "98") (name "/SFI_TX1_P") (class "Default")
      (node (ref "U1") (pin "N14") (pinfunction "TXOUT1P_N14") (pintype "output"))
    )
    (net (code "99") (name "/VDD12_0") (class "Default")
      (node (ref "C110") (pin "2") (pinfunction "2_2") (pintype "passive"))
      (node (ref "C46") (pin "2") (pinfunction "2_2") (pintype "passive"))
      (node (ref "C63") (pin "2") (pinfunction "2_2") (pintype "passive"))
      (node (ref "C64") (pin "2") (pinfunction "2_2") (pintype "passive"))
      (node (ref "C65") (pin "2") (pinfunction "2_2") (pintype "passive"))
      (node (ref "C66") (pin "2") (pinfunction "2_2") (pintype "passive"))
      (node (ref "C67") (pin "2") (pinfunction "2_2") (pintype "passive"))
      (node (ref "C68") (pin "2") (pinfunction "2_2") (pintype "passive"))
      (node (ref "L1") (pin "2") (pinfunction "2_2") (pintype "passive"))
      (node (ref "U1") (pin "F7") (pinfunction "VDD12TX0_F7") (pintype "power_in"))
      (node (ref "U1") (pin "G4") (pinfunction "VDD12X0_G4") (pintype "power_in"))
      (node (ref "U1") (pin "G5") (pinfunction "VDD12X0_G5") (pintype "power_in"))
      (node (ref "U1") (pin "G9") (pinfunction "VDD12TX0_G9") (pintype "power_in"))
      (node (ref "U1") (pin "H9") (pinfunction "VDD12TX1_H9") (pintype "power_in"))
      (node (ref "U1") (pin "J4") (pinfunction "VDD12X1_J4") (pintype "power_in"))
      (node (ref "U1") (pin "J5") (pinfunction "VDD12X1_J5") (pintype "power_in"))
      (node (ref "U1") (pin "J7") (pinfunction "VDD12TX1_J7") (pintype "power_in"))
    )
    (net (code "100") (name "/VDD18_0") (class "Default")
      (node (ref "C111") (pin "2") (pinfunction "2_2") (pintype "passive"))
      (node (ref "C114") (pin "2") (pinfunction "2_2") (pintype "passive"))
      (node (ref "C48") (pin "2") (pinfunction "2_2") (pintype "passive"))
      (node (ref "C49") (pin "2") (pinfunction "2_2") (pintype "passive"))
      (node (ref "C50") (pin "2") (pinfunction "2_2") (pintype "passive"))
      (node (ref "C51") (pin "2") (pinfunction "2_2") (pintype "passive"))
      (node (ref "C52") (pin "2") (pinfunction "2_2") (pintype "passive"))
      (node (ref "L2") (pin "2") (pinfunction "2_2") (pintype "passive"))
      (node (ref "U1") (pin "F10") (pinfunction "VDD18RX0_F10") (pintype "power_in"))
      (node (ref "U1") (pin "F9") (pinfunction "VDD18RX0_F9") (pintype "power_in"))
      (node (ref "U1") (pin "G10") (pinfunction "VDD18TX0_G10") (pintype "power_in"))
      (node (ref "U1") (pin "H10") (pinfunction "VDD18TX1_H10") (pintype "power_in"))
      (node (ref "U1") (pin "J10") (pinfunction "VDD18RX1_J10") (pintype "power_in"))
      (node (ref "U1") (pin "J9") (pinfunction "VDD18RX1_J9") (pintype "power_in"))
    )
    (net (code "101") (name "/VDDCLK_0") (class "Default")
      (node (ref "C57") (pin "2") (pinfunction "2_2") (pintype "passive"))
      (node (ref "C59") (pin "2") (pinfunction "2_2") (pintype "passive"))
      (node (ref "L3") (pin "2") (pinfunction "2_2") (pintype "passive"))
      (node (ref "U1") (pin "G7") (pinfunction "VDDCLK_G7") (pintype "power_in"))
    )
    (net (code "102") (name "/XAUI_CLK0_N") (class "Default")
      (node (ref "U1") (pin "F14") (pinfunction "XREFCKN_F14") (pintype "input"))
    )
    (net (code "103") (name "/XAUI_CLK0_P") (class "Default")
      (node (ref "U1") (pin "F13") (pinfunction "XREFCKP_F13") (pintype "input"))
    )
    (net (code "104") (name "1V2_0") (class "Default")
      (node (ref "C45") (pin "2") (pinfunction "2_2") (pintype "passive"))
      (node (ref "C53") (pin "2") (pinfunction "2_2") (pintype "passive"))
      (node (ref "C54") (pin "2") (pinfunction "2_2") (pintype "passive"))
      (node (ref "C55") (pin "2") (pinfunction "2_2") (pintype "passive"))
      (node (ref "C56") (pin "2") (pinfunction "2_2") (pintype "passive"))
      (node (ref "L1") (pin "1") (pinfunction "1_1") (pintype "passive"))
      (node (ref "L3") (pin "1") (pinfunction "1_1") (pintype "passive"))
      (node (ref "U1") (pin "H4") (pinfunction "VDDB12_H4") (pintype "power_in"))
      (node (ref "U1") (pin "H5") (pinfunction "VDDB12_H5") (pintype "power_in"))
      (node (ref "U1") (pin "H7") (pinfunction "VDDB12_H7") (pintype "power_in"))
    )
    (net (code "105") (name "1V5") (class "Default")
      (node (ref "C60") (pin "2") (pinfunction "2_2") (pintype "passive"))
      (node (ref "U1") (pin "C7") (pinfunction "VDDMDIO_C7") (pintype "power_in"))
    )
    (net (code "106") (name "1V8") (class "Default")
      (node (ref "C47") (pin "2") (pinfunction "2_2") (pintype "passive"))
      (node (ref "L2") (pin "1") (pinfunction "1_1") (pintype "passive"))
    )
    (net (code "107") (name "3V3") (class "Default")
      (node (ref "C69") (pin "2") (pinfunction "2_2") (pintype "passive"))
      (node (ref "C70") (pin "2") (pinfunction "2_2") (pintype "passive"))
      (node (ref "R14") (pin "2") (pinfunction "2_2") (pintype "passive"))
      (node (ref "R15") (pin "2") (pinfunction "2_2") (pintype "passive"))
      (node (ref "U1") (pin "C9") (pinfunction "VDDTTLU_C9") (pintype "power_in"))
      (node (ref "U1") (pin "M6") (pinfunction "VDDTTLL_M6") (pintype "power_in"))
      (node (ref "U5") (pin "8") (pinfunction "VCC_8") (pintype "passive"))
    )
    (net (code "108") (name "GND") (class "Default")
      (node (ref "C110") (pin "1") (pinfunction "1_1") (pintype "passive"))
      (node (ref "C111") (pin "1") (pinfunction "1_1") (pintype "passive"))
      (node (ref "C114") (pin "1") (pinfunction "1_1") (pintype "passive"))
      (node (ref "C45") (pin "1") (pinfunction "1_1") (pintype "passive"))
      (node (ref "C46") (pin "1") (pinfunction "1_1") (pintype "passive"))
      (node (ref "C47") (pin "1") (pinfunction "1_1") (pintype "passive"))
      (node (ref "C48") (pin "1") (pinfunction "1_1") (pintype "passive"))
      (node (ref "C49") (pin "1") (pinfunction "1_1") (pintype "passive"))
      (node (ref "C50") (pin "1") (pinfunction "1_1") (pintype "passive"))
      (node (ref "C51") (pin "1") (pinfunction "1_1") (pintype "passive"))
      (node (ref "C52") (pin "1") (pinfunction "1_1") (pintype "passive"))
      (node (ref "C53") (pin "1") (pinfunction "1_1") (pintype "passive"))
      (node (ref "C54") (pin "1") (pinfunction "1_1") (pintype "passive"))
      (node (ref "C55") (pin "1") (pinfunction "1_1") (pintype "passive"))
      (node (ref "C56") (pin "1") (pinfunction "1_1") (pintype "passive"))
      (node (ref "C57") (pin "1") (pinfunction "1_1") (pintype "passive"))
      (node (ref "C59") (pin "1") (pinfunction "1_1") (pintype "passive"))
      (node (ref "C60") (pin "1") (pinfunction "1_1") (pintype "passive"))
      (node (ref "C63") (pin "1") (pinfunction "1_1") (pintype "passive"))
      (node (ref "C64") (pin "1") (pinfunction "1_1") (pintype "passive"))
      (node (ref "C65") (pin "1") (pinfunction "1_1") (pintype "passive"))
      (node (ref "C66") (pin "1") (pinfunction "1_1") (pintype "passive"))
      (node (ref "C67") (pin "1") (pinfunction "1_1") (pintype "passive"))
      (node (ref "C68") (pin "1") (pinfunction "1_1") (pintype "passive"))
      (node (ref "C69") (pin "1") (pinfunction "1_1") (pintype "passive"))
      (node (ref "C70") (pin "1") (pinfunction "1_1") (pintype "passive"))
      (node (ref "C71") (pin "2") (pinfunction "2_2") (pintype "passive"))
      (node (ref "C72") (pin "2") (pinfunction "2_2") (pintype "passive"))
      (node (ref "C74") (pin "2") (pinfunction "2_2") (pintype "passive"))
      (node (ref "C75") (pin "2") (pinfunction "2_2") (pintype "passive"))
      (node (ref "C76") (pin "2") (pinfunction "2_2") (pintype "passive"))
      (node (ref "C77") (pin "2") (pinfunction "2_2") (pintype "passive"))
      (node (ref "C78") (pin "2") (pinfunction "2_2") (pintype "passive"))
      (node (ref "C79") (pin "1") (pinfunction "1_1") (pintype "passive"))
      (node (ref "C80") (pin "1") (pinfunction "1_1") (pintype "passive"))
      (node (ref "Q1") (pin "2") (pinfunction "S_2") (pintype "passive"))
      (node (ref "Q4") (pin "2") (pinfunction "S_2") (pintype "passive"))
      (node (ref "R12") (pin "1") (pinfunction "1_1") (pintype "passive"))
      (node (ref "R13") (pin "1") (pinfunction "1_1") (pintype "passive"))
      (node (ref "R16") (pin "2") (pinfunction "2_2") (pintype "passive"))
      (node (ref "R17") (pin "2") (pinfunction "2_2") (pintype "passive"))
      (node (ref "R18") (pin "1") (pinfunction "1_1") (pintype "passive"))
      (node (ref "R52") (pin "2") (pinfunction "2_2") (pintype "passive"))
      (node (ref "R53") (pin "2") (pinfunction "2_2") (pintype "passive"))
      (node (ref "R54") (pin "2") (pinfunction "2_2") (pintype "passive"))
      (node (ref "R55") (pin "2") (pinfunction "2_2") (pintype "passive"))
      (node (ref "R56") (pin "2") (pinfunction "2_2") (pintype "passive"))
      (node (ref "U1") (pin "A1") (pinfunction "GND_A1") (pintype "power_in"))
      (node (ref "U1") (pin "A11") (pinfunction "GND_A11") (pintype "power_in"))
      (node (ref "U1") (pin "A12") (pinfunction "GND_A12") (pintype "power_in"))
      (node (ref "U1") (pin "A13") (pinfunction "GND_A13") (pintype "power_in"))
      (node (ref "U1") (pin "A14") (pinfunction "GND_A14") (pintype "power_in"))
      (node (ref "U1") (pin "A2") (pinfunction "GND_A2") (pintype "power_in"))
      (node (ref "U1") (pin "A9") (pinfunction "GND_A9") (pintype "power_in"))
      (node (ref "U1") (pin "B1") (pinfunction "GND_B1") (pintype "power_in"))
      (node (ref "U1") (pin "B11") (pinfunction "GND_B11") (pintype "power_in"))
      (node (ref "U1") (pin "B12") (pinfunction "GND_B12") (pintype "power_in"))
      (node (ref "U1") (pin "B2") (pinfunction "GND_B2") (pintype "power_in"))
      (node (ref "U1") (pin "B9") (pinfunction "GND_B9") (pintype "power_in"))
      (node (ref "U1") (pin "C12") (pinfunction "GND_C12") (pintype "power_in"))
      (node (ref "U1") (pin "C13") (pinfunction "GND_C13") (pintype "power_in"))
      (node (ref "U1") (pin "C14") (pinfunction "GND_C14") (pintype "power_in"))
      (node (ref "U1") (pin "C4") (pinfunction "GND_C4") (pintype "power_in"))
      (node (ref "U1") (pin "C5") (pinfunction "GND_C5") (pintype "power_in"))
      (node (ref "U1") (pin "D12") (pinfunction "GND_D12") (pintype "power_in"))
      (node (ref "U1") (pin "D3") (pinfunction "GND_D3") (pintype "power_in"))
      (node (ref "U1") (pin "E12") (pinfunction "GND_E12") (pintype "power_in"))
      (node (ref "U1") (pin "E13") (pinfunction "GND_E13") (pintype "power_in"))
      (node (ref "U1") (pin "E14") (pinfunction "GND_E14") (pintype "power_in"))
      (node (ref "U1") (pin "E3") (pinfunction "GND_E3") (pintype "power_in"))
      (node (ref "U1") (pin "F11") (pinfunction "GND_F11") (pintype "power_in"))
      (node (ref "U1") (pin "F12") (pinfunction "GND_F12") (pintype "power_in"))
      (node (ref "U1") (pin "F3") (pinfunction "GND_F3") (pintype "power_in"))
      (node (ref "U1") (pin "F6") (pinfunction "GND_F6") (pintype "power_in"))
      (node (ref "U1") (pin "F8") (pinfunction "GND_F8") (pintype "power_in"))
      (node (ref "U1") (pin "G1") (pinfunction "GND_G1") (pintype "power_in"))
      (node (ref "U1") (pin "G11") (pinfunction "GND_G11") (pintype "power_in"))
      (node (ref "U1") (pin "G12") (pinfunction "GND_G12") (pintype "power_in"))
      (node (ref "U1") (pin "G13") (pinfunction "GND_G13") (pintype "power_in"))
      (node (ref "U1") (pin "G14") (pinfunction "GND_G14") (pintype "power_in"))
      (node (ref "U1") (pin "G2") (pinfunction "GND_G2") (pintype "power_in"))
      (node (ref "U1") (pin "G3") (pinfunction "GND_G3") (pintype "power_in"))
      (node (ref "U1") (pin "G6") (pinfunction "GND_G6") (pintype "power_in"))
      (node (ref "U1") (pin "G8") (pinfunction "GND_G8") (pintype "power_in"))
      (node (ref "U1") (pin "H11") (pinfunction "GND_H11") (pintype "power_in"))
      (node (ref "U1") (pin "H13") (pinfunction "GND_H13") (pintype "power_in"))
      (node (ref "U1") (pin "H3") (pinfunction "GND_H3") (pintype "power_in"))
      (node (ref "U1") (pin "H6") (pinfunction "GND_H6") (pintype "power_in"))
      (node (ref "U1") (pin "H8") (pinfunction "GND_H8") (pintype "power_in"))
      (node (ref "U1") (pin "J11") (pinfunction "GND_J11") (pintype "power_in"))
      (node (ref "U1") (pin "J13") (pinfunction "GND_J13") (pintype "power_in"))
      (node (ref "U1") (pin "J3") (pinfunction "GND_J3") (pintype "power_in"))
      (node (ref "U1") (pin "J6") (pinfunction "GND_J6") (pintype "power_in"))
      (node (ref "U1") (pin "J8") (pinfunction "GND_J8") (pintype "power_in"))
      (node (ref "U1") (pin "K12") (pinfunction "GND_K12") (pintype "power_in"))
      (node (ref "U1") (pin "K13") (pinfunction "GND_K13") (pintype "power_in"))
      (node (ref "U1") (pin "K14") (pinfunction "GND_K14") (pintype "power_in"))
      (node (ref "U1") (pin "K3") (pinfunction "GND_K3") (pintype "power_in"))
      (node (ref "U1") (pin "L12") (pinfunction "GND_L12") (pintype "power_in"))
      (node (ref "U1") (pin "L3") (pinfunction "GND_L3") (pintype "power_in"))
      (node (ref "U1") (pin "L9") (pinfunction "SCAN_EN_L9") (pintype "input"))
      (node (ref "U1") (pin "M1") (pinfunction "GND_M1") (pintype "power_in"))
      (node (ref "U1") (pin "M12") (pinfunction "GND_M12") (pintype "power_in"))
      (node (ref "U1") (pin "M13") (pinfunction "GND_M13") (pintype "power_in"))
      (node (ref "U1") (pin "M14") (pinfunction "GND_M14") (pintype "power_in"))
      (node (ref "U1") (pin "M2") (pinfunction "GND_M2") (pintype "power_in"))
      (node (ref "U1") (pin "M4") (pinfunction "GND_M4") (pintype "power_in"))
      (node (ref "U1") (pin "N1") (pinfunction "GND_N1") (pintype "power_in"))
      (node (ref "U1") (pin "N10") (pinfunction "GND_N10") (pintype "power_in"))
      (node (ref "U1") (pin "N12") (pinfunction "GND_N12") (pintype "power_in"))
      (node (ref "U1") (pin "N6") (pinfunction "GND_N6") (pintype "power_in"))
      (node (ref "U1") (pin "N8") (pinfunction "GND_N8") (pintype "power_in"))
      (node (ref "U1") (pin "P1") (pinfunction "GND_P1") (pintype "power_in"))
      (node (ref "U1") (pin "P10") (pinfunction "GND_P10") (pintype "power_in"))
      (node (ref "U1") (pin "P12") (pinfunction "GND_P12") (pintype "power_in"))
      (node (ref "U1") (pin "P13") (pinfunction "GND_P13") (pintype "power_in"))
      (node (ref "U1") (pin "P14") (pinfunction "GND_P14") (pintype "power_in"))
      (node (ref "U1") (pin "P6") (pinfunction "GND_P6") (pintype "power_in"))
      (node (ref "U1") (pin "P8") (pinfunction "GND_P8") (pintype "power_in"))
      (node (ref "U5") (pin "2") (pinfunction "A1_2") (pintype "input"))
      (node (ref "U5") (pin "3") (pinfunction "A2_3") (pintype "input"))
      (node (ref "U5") (pin "4") (pinfunction "GND_4") (pintype "passive"))
    )
    (net (code "109") (name "Net-(Q1-D)") (class "Default")
      (node (ref "Q1") (pin "3") (pinfunction "D_3") (pintype "passive"))
      (node (ref "U1") (pin "C6") (pinfunction "RESETN_C6") (pintype "input"))
    )
    (net (code "110") (name "Net-(U1B-CMUFILT0)") (class "Default")
      (node (ref "C75") (pin "1") (pinfunction "1_1") (pintype "passive"))
      (node (ref "U1") (pin "E11") (pinfunction "CMUFILT0_E11") (pintype "passive"))
    )
    (net (code "111") (name "Net-(U1B-CMUFILT1)") (class "Default")
      (node (ref "C76") (pin "1") (pinfunction "1_1") (pintype "passive"))
      (node (ref "U1") (pin "P11") (pinfunction "CMUFILT1_P11") (pintype "passive"))
    )
    (net (code "112") (name "Net-(U1B-CMUFILTER)") (class "Default")
      (node (ref "C74") (pin "1") (pinfunction "1_1") (pintype "passive"))
      (node (ref "U1") (pin "L11") (pinfunction "CMUFILTER_L11") (pintype "passive"))
    )
    (net (code "113") (name "Net-(U1B-RXCRUFILT0)") (class "Default")
      (node (ref "C77") (pin "1") (pinfunction "1_1") (pintype "passive"))
      (node (ref "U1") (pin "C11") (pinfunction "RXCRUFILT0_C11") (pintype "passive"))
    )
    (net (code "114") (name "Net-(U1B-RXCRUFILT1)") (class "Default")
      (node (ref "C78") (pin "1") (pinfunction "1_1") (pintype "passive"))
      (node (ref "U1") (pin "M11") (pinfunction "RXCRUFILT1_M11") (pintype "passive"))
    )
    (net (code "115") (name "Net-(U1B-RXINCM0)") (class "Default")
      (node (ref "C79") (pin "2") (pinfunction "2_2") (pintype "passive"))
      (node (ref "U1") (pin "D11") (pinfunction "RXINCM0_D11") (pintype "passive"))
    )
    (net (code "116") (name "Net-(U1B-RXINCM1)") (class "Default")
      (node (ref "C80") (pin "2") (pinfunction "2_2") (pintype "passive"))
      (node (ref "U1") (pin "N11") (pinfunction "RXINCM1_N11") (pintype "passive"))
    )
    (net (code "117") (name "Net-(U1C-XAUIFILT0)") (class "Default")
      (node (ref "C72") (pin "1") (pinfunction "1_1") (pintype "passive"))
      (node (ref "U1") (pin "C3") (pinfunction "XAUIFILT0_C3") (pintype "passive"))
    )
    (net (code "118") (name "Net-(U1C-XAUIFILT1)") (class "Default")
      (node (ref "C71") (pin "1") (pinfunction "1_1") (pintype "passive"))
      (node (ref "U1") (pin "M3") (pinfunction "XAUIFILT1_M3") (pintype "passive"))
    )
    (net (code "119") (name "Net-(U1D-PADDR1)") (class "Default")
      (node (ref "R53") (pin "1") (pinfunction "1_1") (pintype "passive"))
      (node (ref "U1") (pin "D10") (pinfunction "PADDR1_D10") (pintype "input"))
    )
    (net (code "120") (name "Net-(U1D-PADDR2)") (class "Default")
      (node (ref "R54") (pin "1") (pinfunction "1_1") (pintype "passive"))
      (node (ref "U1") (pin "C8") (pinfunction "PADDR2_C8") (pintype "input"))
    )
    (net (code "121") (name "Net-(U1D-PADDR3)") (class "Default")
      (node (ref "R55") (pin "1") (pinfunction "1_1") (pintype "passive"))
      (node (ref "U1") (pin "E10") (pinfunction "PADDR3_E10") (pintype "input"))
    )
    (net (code "122") (name "Net-(U1D-PADDR4)") (class "Default")
      (node (ref "R56") (pin "1") (pinfunction "1_1") (pintype "passive"))
      (node (ref "U1") (pin "E6") (pinfunction "PADDR4_E6") (pintype "input"))
    )
    (net (code "123") (name "Net-(U1D-STWA0)") (class "Default")
      (node (ref "R16") (pin "1") (pinfunction "1_1") (pintype "passive"))
      (node (ref "U1") (pin "B7") (pinfunction "STWA0_B7") (pintype "input"))
    )
    (net (code "124") (name "Net-(U1D-STWA1)") (class "Default")
      (node (ref "R17") (pin "1") (pinfunction "1_1") (pintype "passive"))
      (node (ref "U1") (pin "A7") (pinfunction "STWA1_A7") (pintype "input"))
    )
    (net (code "125") (name "Net-(U1D-STWA2)") (class "Default")
      (node (ref "R52") (pin "1") (pinfunction "1_1") (pintype "passive"))
      (node (ref "U1") (pin "C10") (pinfunction "STWA2_C10") (pintype "input"))
    )
    (net (code "126") (name "Net-(U1D-TMON)") (class "Default")
      (node (ref "TP3") (pin "1") (pinfunction "1_1") (pintype "passive"))
      (node (ref "U1") (pin "M10") (pinfunction "TMON_M10") (pintype "passive"))
    )
    (net (code "127") (name "Net-(U5-WP)") (class "Default")
      (node (ref "R12") (pin "2") (pinfunction "2_2") (pintype "passive"))
      (node (ref "U5") (pin "7") (pinfunction "WP_7") (pintype "input"))
    )
    (net (code "128") (name "unconnected-(U1B-RX0CKOUTN-PadA8)") (class "Default")
      (node (ref "U1") (pin "A8") (pinfunction "RX0CKOUTN_A8") (pintype "output+no_connect"))
    )
    (net (code "129") (name "unconnected-(U1B-RX0CKOUTP-PadB8)") (class "Default")
      (node (ref "U1") (pin "B8") (pinfunction "RX0CKOUTP_B8") (pintype "output+no_connect"))
    )
    (net (code "130") (name "unconnected-(U1B-RX1CKOUTN-PadP7)") (class "Default")
      (node (ref "U1") (pin "P7") (pinfunction "RX1CKOUTN_P7") (pintype "output+no_connect"))
    )
    (net (code "131") (name "unconnected-(U1B-RX1CKOUTP-PadN7)") (class "Default")
      (node (ref "U1") (pin "N7") (pinfunction "RX1CKOUTP_N7") (pintype "output+no_connect"))
    )
    (net (code "132") (name "unconnected-(U1B-SREFCKN-PadJ12)") (class "Default")
      (node (ref "U1") (pin "J12") (pinfunction "SREFCKN_J12") (pintype "input+no_connect"))
    )
    (net (code "133") (name "unconnected-(U1B-SREFCKP-PadH12)") (class "Default")
      (node (ref "U1") (pin "H12") (pinfunction "SREFCKP_H12") (pintype "input+no_connect"))
    )
    (net (code "134") (name "unconnected-(U1B-TX0CKOUTN-PadA10)") (class "Default")
      (node (ref "U1") (pin "A10") (pinfunction "TX0CKOUTN_A10") (pintype "output+no_connect"))
    )
    (net (code "135") (name "unconnected-(U1B-TX0CKOUTP-PadB10)") (class "Default")
      (node (ref "U1") (pin "B10") (pinfunction "TX0CKOUTP_B10") (pintype "output+no_connect"))
    )
    (net (code "136") (name "unconnected-(U1B-TX1CKOUTN-PadP9)") (class "Default")
      (node (ref "U1") (pin "P9") (pinfunction "TX1CKOUTN_P9") (pintype "output+no_connect"))
    )
    (net (code "137") (name "unconnected-(U1B-TX1CKOUTP-PadN9)") (class "Default")
      (node (ref "U1") (pin "N9") (pinfunction "TX1CKOUTP_N9") (pintype "output+no_connect"))
    )
    (net (code "138") (name "unconnected-(U1B-WREFCKN-PadJ14)") (class "Default")
      (node (ref "U1") (pin "J14") (pinfunction "WREFCKN_J14") (pintype "input+no_connect"))
    )
    (net (code "139") (name "unconnected-(U1B-WREFCKP-PadH14)") (class "Default")
      (node (ref "U1") (pin "H14") (pinfunction "WREFCKP_H14") (pintype "input+no_connect"))
    )
    (net (code "140") (name "unconnected-(U1D-ANATEST-PadM8)") (class "Default")
      (node (ref "U1") (pin "M8") (pinfunction "ANATEST_M8") (pintype "passive+no_connect"))
    )
    (net (code "141") (name "unconnected-(U1D-RSVD1-PadD8)") (class "Default")
      (node (ref "U1") (pin "D8") (pinfunction "RSVD1_D8") (pintype "passive+no_connect"))
    )
    (net (code "142") (name "unconnected-(U1D-RSVD2-PadE8)") (class "Default")
      (node (ref "U1") (pin "E8") (pinfunction "RSVD2_E8") (pintype "passive+no_connect"))
    )
    (net (code "143") (name "unconnected-(U1D-RSVD3-PadK7)") (class "Default")
      (node (ref "U1") (pin "K7") (pinfunction "RSVD3_K7") (pintype "passive+no_connect"))
    )
    (net (code "144") (name "unconnected-(U1D-RSVD4-PadL7)") (class "Default")
      (node (ref "U1") (pin "L7") (pinfunction "RSVD4_L7") (pintype "passive+no_connect"))
    )
    (net (code "145") (name "unconnected-(U1D-TCK-PadK9)") (class "Default")
      (node (ref "U1") (pin "K9") (pinfunction "TCK_K9") (pintype "input+no_connect"))
    )
    (net (code "146") (name "unconnected-(U1D-TDI-PadL8)") (class "Default")
      (node (ref "U1") (pin "L8") (pinfunction "TDI_L8") (pintype "input+no_connect"))
    )
    (net (code "147") (name "unconnected-(U1D-TDO-PadK8)") (class "Default")
      (node (ref "U1") (pin "K8") (pinfunction "TDO_K8") (pintype "output+no_connect"))
    )
    (net (code "148") (name "unconnected-(U1D-TMS-PadM5)") (class "Default")
      (node (ref "U1") (pin "M5") (pinfunction "TMS_M5") (pintype "input+no_connect"))
    )
    (net (code "149") (name "unconnected-(U5-NC-Pad1)") (class "Default")
      (node (ref "U5") (pin "1") (pinfunction "NC_1") (pintype "passive+no_connect"))
    )
  )
)
